# Pattern_Ident_v2.net
KiCad netlist of a schematic drawn in EAGLE
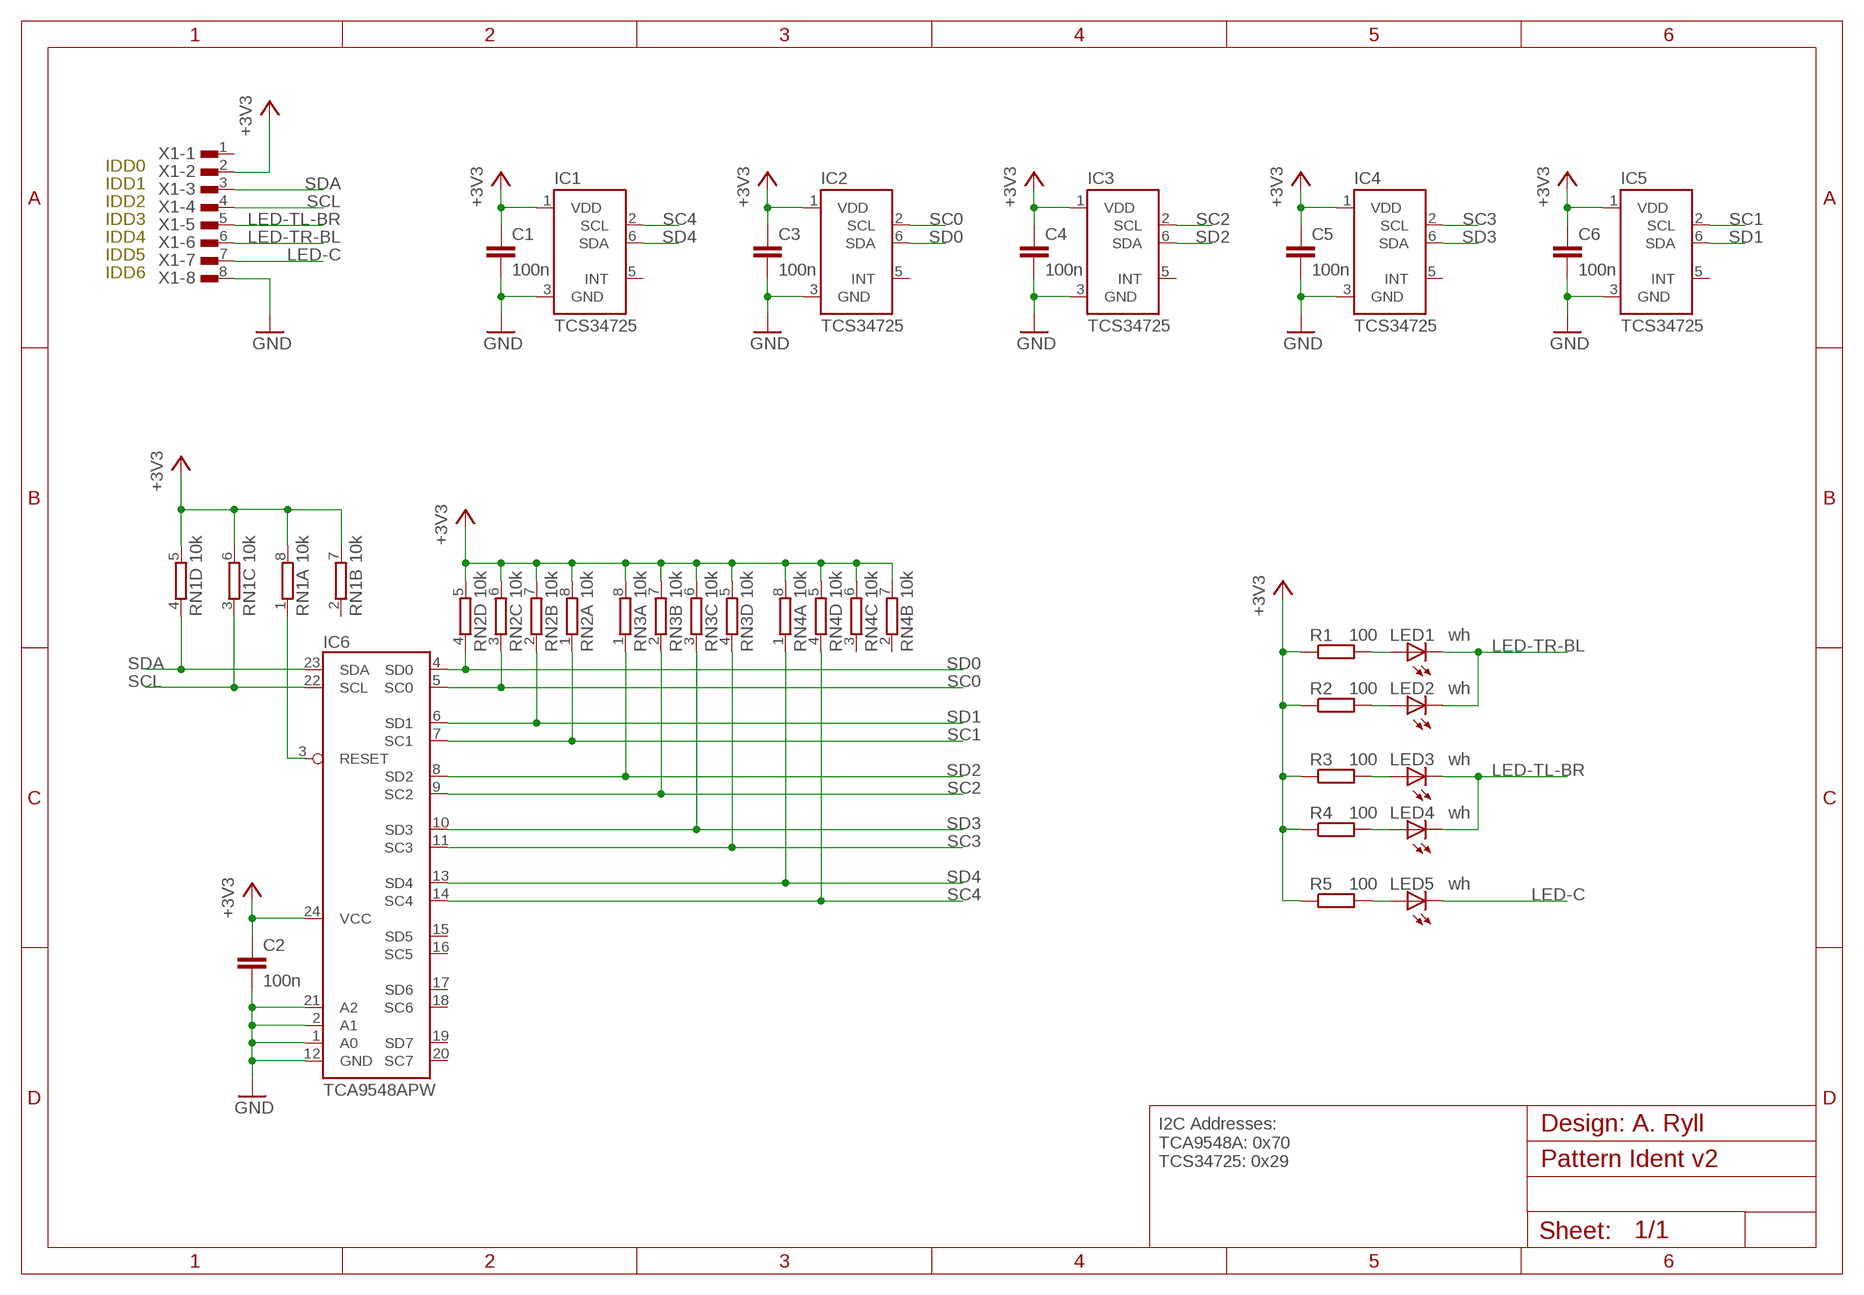
[diagram p0: schematic, sheet 1]

(export (version "E")
  (design (tool "Eeschema 10.0.6"))
  (components
    (comp (ref "C1")
      (value "100n")
      (footprint "eagle-import:C0603")
      (libsource (lib "eagle-import") (part "C-EUC0603"))
    )
    (comp (ref "C2")
      (value "100n")
      (footprint "eagle-import:C0603")
      (libsource (lib "eagle-import") (part "C-EUC0603"))
    )
    (comp (ref "C3")
      (value "100n")
      (footprint "eagle-import:C0603")
      (libsource (lib "eagle-import") (part "C-EUC0603"))
    )
    (comp (ref "C4")
      (value "100n")
      (footprint "eagle-import:C0603")
      (libsource (lib "eagle-import") (part "C-EUC0603"))
    )
    (comp (ref "C5")
      (value "100n")
      (footprint "eagle-import:C0603")
      (libsource (lib "eagle-import") (part "C-EUC0603"))
    )
    (comp (ref "C6")
      (value "100n")
      (footprint "eagle-import:C0603")
      (libsource (lib "eagle-import") (part "C-EUC0603"))
    )
    (comp (ref "IC1")
      (value "TCS34725")
      (footprint "eagle-import:DFN6")
      (libsource (lib "eagle-import") (part "TCS3472"))
    )
    (comp (ref "IC2")
      (value "TCS34725")
      (footprint "eagle-import:DFN6")
      (libsource (lib "eagle-import") (part "TCS3472"))
    )
    (comp (ref "IC3")
      (value "TCS34725")
      (footprint "eagle-import:DFN6")
      (libsource (lib "eagle-import") (part "TCS3472"))
    )
    (comp (ref "IC4")
      (value "TCS34725")
      (footprint "eagle-import:DFN6")
      (libsource (lib "eagle-import") (part "TCS3472"))
    )
    (comp (ref "IC5")
      (value "TCS34725")
      (footprint "eagle-import:DFN6")
      (libsource (lib "eagle-import") (part "TCS3472"))
    )
    (comp (ref "IC6")
      (value "TCA9548APW")
      (footprint "eagle-import:TSSOP24")
      (libsource (lib "eagle-import") (part "TCA9548APW"))
    )
    (comp (ref "LED1")
      (value "wh")
      (footprint "eagle-import:CHIPLED_1206")
      (libsource (lib "eagle-import") (part "LEDCHIPLED_1206"))
    )
    (comp (ref "LED2")
      (value "wh")
      (footprint "eagle-import:CHIPLED_1206")
      (libsource (lib "eagle-import") (part "LEDCHIPLED_1206"))
    )
    (comp (ref "LED3")
      (value "wh")
      (footprint "eagle-import:CHIPLED_1206")
      (libsource (lib "eagle-import") (part "LEDCHIPLED_1206"))
    )
    (comp (ref "LED4")
      (value "wh")
      (footprint "eagle-import:CHIPLED_1206")
      (libsource (lib "eagle-import") (part "LEDCHIPLED_1206"))
    )
    (comp (ref "LED5")
      (value "wh")
      (footprint "eagle-import:CHIPLED_1206")
      (libsource (lib "eagle-import") (part "LEDCHIPLED_1206"))
    )
    (comp (ref "R1")
      (value "100")
      (footprint "eagle-import:R0603")
      (libsource (lib "eagle-import") (part "R-EU_R0603"))
    )
    (comp (ref "R2")
      (value "100")
      (footprint "eagle-import:R0603")
      (libsource (lib "eagle-import") (part "R-EU_R0603"))
    )
    (comp (ref "R3")
      (value "100")
      (footprint "eagle-import:R0603")
      (libsource (lib "eagle-import") (part "R-EU_R0603"))
    )
    (comp (ref "R4")
      (value "100")
      (footprint "eagle-import:R0603")
      (libsource (lib "eagle-import") (part "R-EU_R0603"))
    )
    (comp (ref "R5")
      (value "100")
      (footprint "eagle-import:R0603")
      (libsource (lib "eagle-import") (part "R-EU_R0603"))
    )
    (comp (ref "RN1")
      (value "10k")
      (footprint "eagle-import:EXB28V")
      (libsource (lib "eagle-import") (part "4R-NEXB28V"))
    )
    (comp (ref "RN2")
      (value "10k")
      (footprint "eagle-import:EXB28V")
      (libsource (lib "eagle-import") (part "4R-NEXB28V"))
    )
    (comp (ref "RN3")
      (value "10k")
      (footprint "eagle-import:EXB28V")
      (libsource (lib "eagle-import") (part "4R-NEXB28V"))
    )
    (comp (ref "RN4")
      (value "10k")
      (footprint "eagle-import:EXB28V")
      (libsource (lib "eagle-import") (part "4R-NEXB28V"))
    )
    (comp (ref "X1")
      (value "TE-FPC-1MM-8H")
      (footprint "eagle-import:TE-84952-8")
      (libsource (lib "eagle-import") (part "TE-FPC-1MM-8H"))
    )
  )
  (nets
    (net (code "1") (name "+3V3") (class "Default")
      (node (ref "C1") (pin "1") (pinfunction "1_1") (pintype "passive"))
      (node (ref "C2") (pin "1") (pinfunction "1_1") (pintype "passive"))
      (node (ref "C3") (pin "1") (pinfunction "1_1") (pintype "passive"))
      (node (ref "C4") (pin "1") (pinfunction "1_1") (pintype "passive"))
      (node (ref "C5") (pin "1") (pinfunction "1_1") (pintype "passive"))
      (node (ref "C6") (pin "1") (pinfunction "1_1") (pintype "passive"))
      (node (ref "IC1") (pin "1") (pinfunction "VDD_1") (pintype "bidirectional"))
      (node (ref "IC2") (pin "1") (pinfunction "VDD_1") (pintype "bidirectional"))
      (node (ref "IC3") (pin "1") (pinfunction "VDD_1") (pintype "bidirectional"))
      (node (ref "IC4") (pin "1") (pinfunction "VDD_1") (pintype "bidirectional"))
      (node (ref "IC5") (pin "1") (pinfunction "VDD_1") (pintype "bidirectional"))
      (node (ref "IC6") (pin "24") (pinfunction "VCC_24") (pintype "bidirectional"))
      (node (ref "R1") (pin "1") (pinfunction "1_1") (pintype "passive"))
      (node (ref "R2") (pin "1") (pinfunction "1_1") (pintype "passive"))
      (node (ref "R3") (pin "1") (pinfunction "1_1") (pintype "passive"))
      (node (ref "R4") (pin "1") (pinfunction "1_1") (pintype "passive"))
      (node (ref "R5") (pin "1") (pinfunction "1_1") (pintype "passive"))
      (node (ref "RN1") (pin "5") (pinfunction "2_5") (pintype "passive"))
      (node (ref "RN1") (pin "6") (pinfunction "2_6") (pintype "passive"))
      (node (ref "RN1") (pin "7") (pinfunction "2_7") (pintype "passive"))
      (node (ref "RN1") (pin "8") (pinfunction "2_8") (pintype "passive"))
      (node (ref "RN2") (pin "5") (pinfunction "2_5") (pintype "passive"))
      (node (ref "RN2") (pin "6") (pinfunction "2_6") (pintype "passive"))
      (node (ref "RN2") (pin "7") (pinfunction "2_7") (pintype "passive"))
      (node (ref "RN2") (pin "8") (pinfunction "2_8") (pintype "passive"))
      (node (ref "RN3") (pin "5") (pinfunction "2_5") (pintype "passive"))
      (node (ref "RN3") (pin "6") (pinfunction "2_6") (pintype "passive"))
      (node (ref "RN3") (pin "7") (pinfunction "2_7") (pintype "passive"))
      (node (ref "RN3") (pin "8") (pinfunction "2_8") (pintype "passive"))
      (node (ref "RN4") (pin "5") (pinfunction "2_5") (pintype "passive"))
      (node (ref "RN4") (pin "6") (pinfunction "2_6") (pintype "passive"))
      (node (ref "RN4") (pin "7") (pinfunction "2_7") (pintype "passive"))
      (node (ref "RN4") (pin "8") (pinfunction "2_8") (pintype "passive"))
      (node (ref "X1") (pin "2") (pinfunction "-1_2") (pintype "bidirectional"))
    )
    (net (code "9") (name "/LED-C") (class "Default")
      (node (ref "LED5") (pin "C") (pinfunction "C_C") (pintype "passive"))
      (node (ref "X1") (pin "7") (pinfunction "-1_7") (pintype "bidirectional"))
    )
    (net (code "10") (name "/LED-TL-BR") (class "Default")
      (node (ref "LED3") (pin "C") (pinfunction "C_C") (pintype "passive"))
      (node (ref "LED4") (pin "C") (pinfunction "C_C") (pintype "passive"))
      (node (ref "X1") (pin "5") (pinfunction "-1_5") (pintype "bidirectional"))
    )
    (net (code "11") (name "/LED-TR-BL") (class "Default")
      (node (ref "LED1") (pin "C") (pinfunction "C_C") (pintype "passive"))
      (node (ref "LED2") (pin "C") (pinfunction "C_C") (pintype "passive"))
      (node (ref "X1") (pin "6") (pinfunction "-1_6") (pintype "bidirectional"))
    )
    (net (code "12") (name "/SC0") (class "Default")
      (node (ref "IC2") (pin "2") (pinfunction "SCL_2") (pintype "bidirectional"))
      (node (ref "IC6") (pin "5") (pinfunction "SC0_5") (pintype "bidirectional"))
      (node (ref "RN2") (pin "3") (pinfunction "1_3") (pintype "passive"))
    )
    (net (code "13") (name "/SC1") (class "Default")
      (node (ref "IC5") (pin "2") (pinfunction "SCL_2") (pintype "bidirectional"))
      (node (ref "IC6") (pin "7") (pinfunction "SC1_7") (pintype "bidirectional"))
      (node (ref "RN2") (pin "1") (pinfunction "1_1") (pintype "passive"))
    )
    (net (code "14") (name "/SC2") (class "Default")
      (node (ref "IC3") (pin "2") (pinfunction "SCL_2") (pintype "bidirectional"))
      (node (ref "IC6") (pin "9") (pinfunction "SC2_9") (pintype "bidirectional"))
      (node (ref "RN3") (pin "2") (pinfunction "1_2") (pintype "passive"))
    )
    (net (code "15") (name "/SC3") (class "Default")
      (node (ref "IC4") (pin "2") (pinfunction "SCL_2") (pintype "bidirectional"))
      (node (ref "IC6") (pin "11") (pinfunction "SC3_11") (pintype "bidirectional"))
      (node (ref "RN3") (pin "4") (pinfunction "1_4") (pintype "passive"))
    )
    (net (code "16") (name "/SC4") (class "Default")
      (node (ref "IC1") (pin "2") (pinfunction "SCL_2") (pintype "bidirectional"))
      (node (ref "IC6") (pin "14") (pinfunction "SC4_14") (pintype "bidirectional"))
      (node (ref "RN4") (pin "4") (pinfunction "1_4") (pintype "passive"))
    )
    (net (code "17") (name "/SCL") (class "Default")
      (node (ref "IC6") (pin "22") (pinfunction "SCL_22") (pintype "bidirectional"))
      (node (ref "RN1") (pin "3") (pinfunction "1_3") (pintype "passive"))
      (node (ref "X1") (pin "4") (pinfunction "-1_4") (pintype "bidirectional"))
    )
    (net (code "18") (name "/SD0") (class "Default")
      (node (ref "IC2") (pin "6") (pinfunction "SDA_6") (pintype "bidirectional"))
      (node (ref "IC6") (pin "4") (pinfunction "SD0_4") (pintype "bidirectional"))
      (node (ref "RN2") (pin "4") (pinfunction "1_4") (pintype "passive"))
    )
    (net (code "19") (name "/SD1") (class "Default")
      (node (ref "IC5") (pin "6") (pinfunction "SDA_6") (pintype "bidirectional"))
      (node (ref "IC6") (pin "6") (pinfunction "SD1_6") (pintype "bidirectional"))
      (node (ref "RN2") (pin "2") (pinfunction "1_2") (pintype "passive"))
    )
    (net (code "20") (name "/SD2") (class "Default")
      (node (ref "IC3") (pin "6") (pinfunction "SDA_6") (pintype "bidirectional"))
      (node (ref "IC6") (pin "8") (pinfunction "SD2_8") (pintype "bidirectional"))
      (node (ref "RN3") (pin "1") (pinfunction "1_1") (pintype "passive"))
    )
    (net (code "21") (name "/SD3") (class "Default")
      (node (ref "IC4") (pin "6") (pinfunction "SDA_6") (pintype "bidirectional"))
      (node (ref "IC6") (pin "10") (pinfunction "SD3_10") (pintype "bidirectional"))
      (node (ref "RN3") (pin "3") (pinfunction "1_3") (pintype "passive"))
    )
    (net (code "22") (name "/SD4") (class "Default")
      (node (ref "IC1") (pin "6") (pinfunction "SDA_6") (pintype "bidirectional"))
      (node (ref "IC6") (pin "13") (pinfunction "SD4_13") (pintype "bidirectional"))
      (node (ref "RN4") (pin "1") (pinfunction "1_1") (pintype "passive"))
    )
    (net (code "23") (name "/SDA") (class "Default")
      (node (ref "IC6") (pin "23") (pinfunction "SDA_23") (pintype "bidirectional"))
      (node (ref "RN1") (pin "4") (pinfunction "1_4") (pintype "passive"))
      (node (ref "X1") (pin "3") (pinfunction "-1_3") (pintype "bidirectional"))
    )
    (net (code "24") (name "GND") (class "Default")
      (node (ref "C1") (pin "2") (pinfunction "2_2") (pintype "passive"))
      (node (ref "C2") (pin "2") (pinfunction "2_2") (pintype "passive"))
      (node (ref "C3") (pin "2") (pinfunction "2_2") (pintype "passive"))
      (node (ref "C4") (pin "2") (pinfunction "2_2") (pintype "passive"))
      (node (ref "C5") (pin "2") (pinfunction "2_2") (pintype "passive"))
      (node (ref "C6") (pin "2") (pinfunction "2_2") (pintype "passive"))
      (node (ref "IC1") (pin "3") (pinfunction "GND_3") (pintype "bidirectional"))
      (node (ref "IC2") (pin "3") (pinfunction "GND_3") (pintype "bidirectional"))
      (node (ref "IC3") (pin "3") (pinfunction "GND_3") (pintype "bidirectional"))
      (node (ref "IC4") (pin "3") (pinfunction "GND_3") (pintype "bidirectional"))
      (node (ref "IC5") (pin "3") (pinfunction "GND_3") (pintype "bidirectional"))
      (node (ref "IC6") (pin "1") (pinfunction "A0_1") (pintype "bidirectional"))
      (node (ref "IC6") (pin "12") (pinfunction "GND_12") (pintype "bidirectional"))
      (node (ref "IC6") (pin "2") (pinfunction "A1_2") (pintype "bidirectional"))
      (node (ref "IC6") (pin "21") (pinfunction "A2_21") (pintype "bidirectional"))
      (node (ref "X1") (pin "8") (pinfunction "-1_8") (pintype "bidirectional"))
    )
    (net (code "25") (name "Net-(IC6-RESET)") (class "Default")
      (node (ref "IC6") (pin "3") (pinfunction "RESET_3") (pintype "bidirectional"))
      (node (ref "RN1") (pin "1") (pinfunction "1_1") (pintype "passive"))
    )
    (net (code "26") (name "Net-(LED1-PadA)") (class "Default")
      (node (ref "LED1") (pin "A") (pinfunction "A_A") (pintype "passive"))
      (node (ref "R1") (pin "2") (pinfunction "2_2") (pintype "passive"))
    )
    (net (code "27") (name "Net-(LED2-PadA)") (class "Default")
      (node (ref "LED2") (pin "A") (pinfunction "A_A") (pintype "passive"))
      (node (ref "R2") (pin "2") (pinfunction "2_2") (pintype "passive"))
    )
    (net (code "28") (name "Net-(LED3-PadA)") (class "Default")
      (node (ref "LED3") (pin "A") (pinfunction "A_A") (pintype "passive"))
      (node (ref "R3") (pin "2") (pinfunction "2_2") (pintype "passive"))
    )
    (net (code "29") (name "Net-(LED4-PadA)") (class "Default")
      (node (ref "LED4") (pin "A") (pinfunction "A_A") (pintype "passive"))
      (node (ref "R4") (pin "2") (pinfunction "2_2") (pintype "passive"))
    )
    (net (code "30") (name "Net-(LED5-PadA)") (class "Default")
      (node (ref "LED5") (pin "A") (pinfunction "A_A") (pintype "passive"))
      (node (ref "R5") (pin "2") (pinfunction "2_2") (pintype "passive"))
    )
    (net (code "31") (name "unconnected-(IC1-INT-Pad5)") (class "Default")
      (node (ref "IC1") (pin "5") (pinfunction "INT_5") (pintype "bidirectional"))
    )
    (net (code "32") (name "unconnected-(IC2-INT-Pad5)") (class "Default")
      (node (ref "IC2") (pin "5") (pinfunction "INT_5") (pintype "bidirectional"))
    )
    (net (code "33") (name "unconnected-(IC3-INT-Pad5)") (class "Default")
      (node (ref "IC3") (pin "5") (pinfunction "INT_5") (pintype "bidirectional"))
    )
    (net (code "34") (name "unconnected-(IC4-INT-Pad5)") (class "Default")
      (node (ref "IC4") (pin "5") (pinfunction "INT_5") (pintype "bidirectional"))
    )
    (net (code "35") (name "unconnected-(IC5-INT-Pad5)") (class "Default")
      (node (ref "IC5") (pin "5") (pinfunction "INT_5") (pintype "bidirectional"))
    )
    (net (code "36") (name "unconnected-(IC6-SC5-Pad16)") (class "Default")
      (node (ref "IC6") (pin "16") (pinfunction "SC5_16") (pintype "bidirectional"))
    )
    (net (code "37") (name "unconnected-(IC6-SC6-Pad18)") (class "Default")
      (node (ref "IC6") (pin "18") (pinfunction "SC6_18") (pintype "bidirectional"))
    )
    (net (code "38") (name "unconnected-(IC6-SC7-Pad20)") (class "Default")
      (node (ref "IC6") (pin "20") (pinfunction "SC7_20") (pintype "bidirectional"))
    )
    (net (code "39") (name "unconnected-(IC6-SD5-Pad15)") (class "Default")
      (node (ref "IC6") (pin "15") (pinfunction "SD5_15") (pintype "bidirectional"))
    )
    (net (code "40") (name "unconnected-(IC6-SD6-Pad17)") (class "Default")
      (node (ref "IC6") (pin "17") (pinfunction "SD6_17") (pintype "bidirectional"))
    )
    (net (code "41") (name "unconnected-(IC6-SD7-Pad19)") (class "Default")
      (node (ref "IC6") (pin "19") (pinfunction "SD7_19") (pintype "bidirectional"))
    )
    (net (code "42") (name "unconnected-(RN1B-1-Pad2)") (class "Default")
      (node (ref "RN1") (pin "2") (pinfunction "1_2") (pintype "passive"))
    )
    (net (code "43") (name "unconnected-(RN4B-1-Pad2)") (class "Default")
      (node (ref "RN4") (pin "2") (pinfunction "1_2") (pintype "passive"))
    )
    (net (code "44") (name "unconnected-(RN4C-1-Pad3)") (class "Default")
      (node (ref "RN4") (pin "3") (pinfunction "1_3") (pintype "passive"))
    )
    (net (code "45") (name "unconnected-(X1A--1-Pad1)") (class "Default")
      (node (ref "X1") (pin "1") (pinfunction "-1_1") (pintype "bidirectional"))
    )
  )
)
